# remote_control.net
KiCad netlist of a schematic drawn in EAGLE
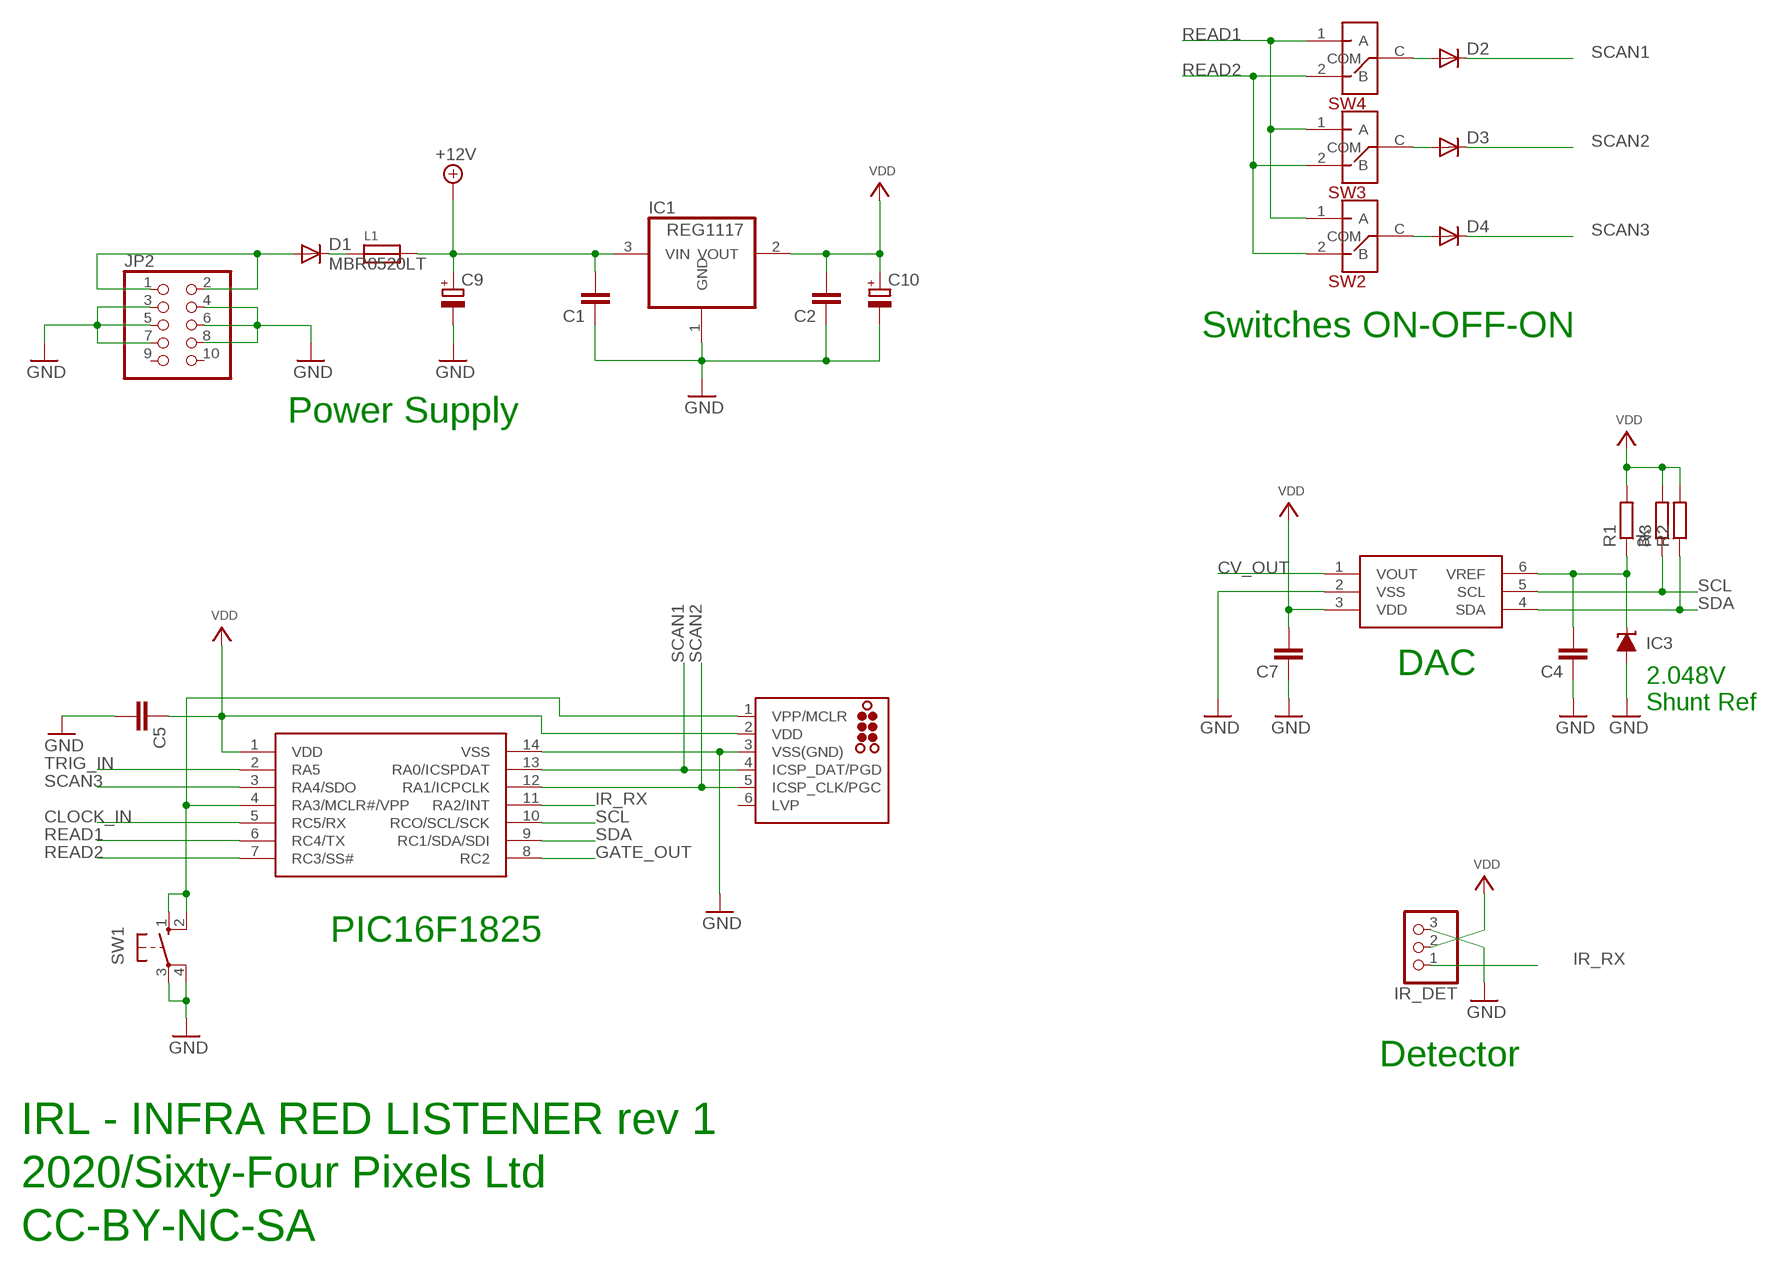
[diagram p0: schematic, sheet 1, part 1 of 2]
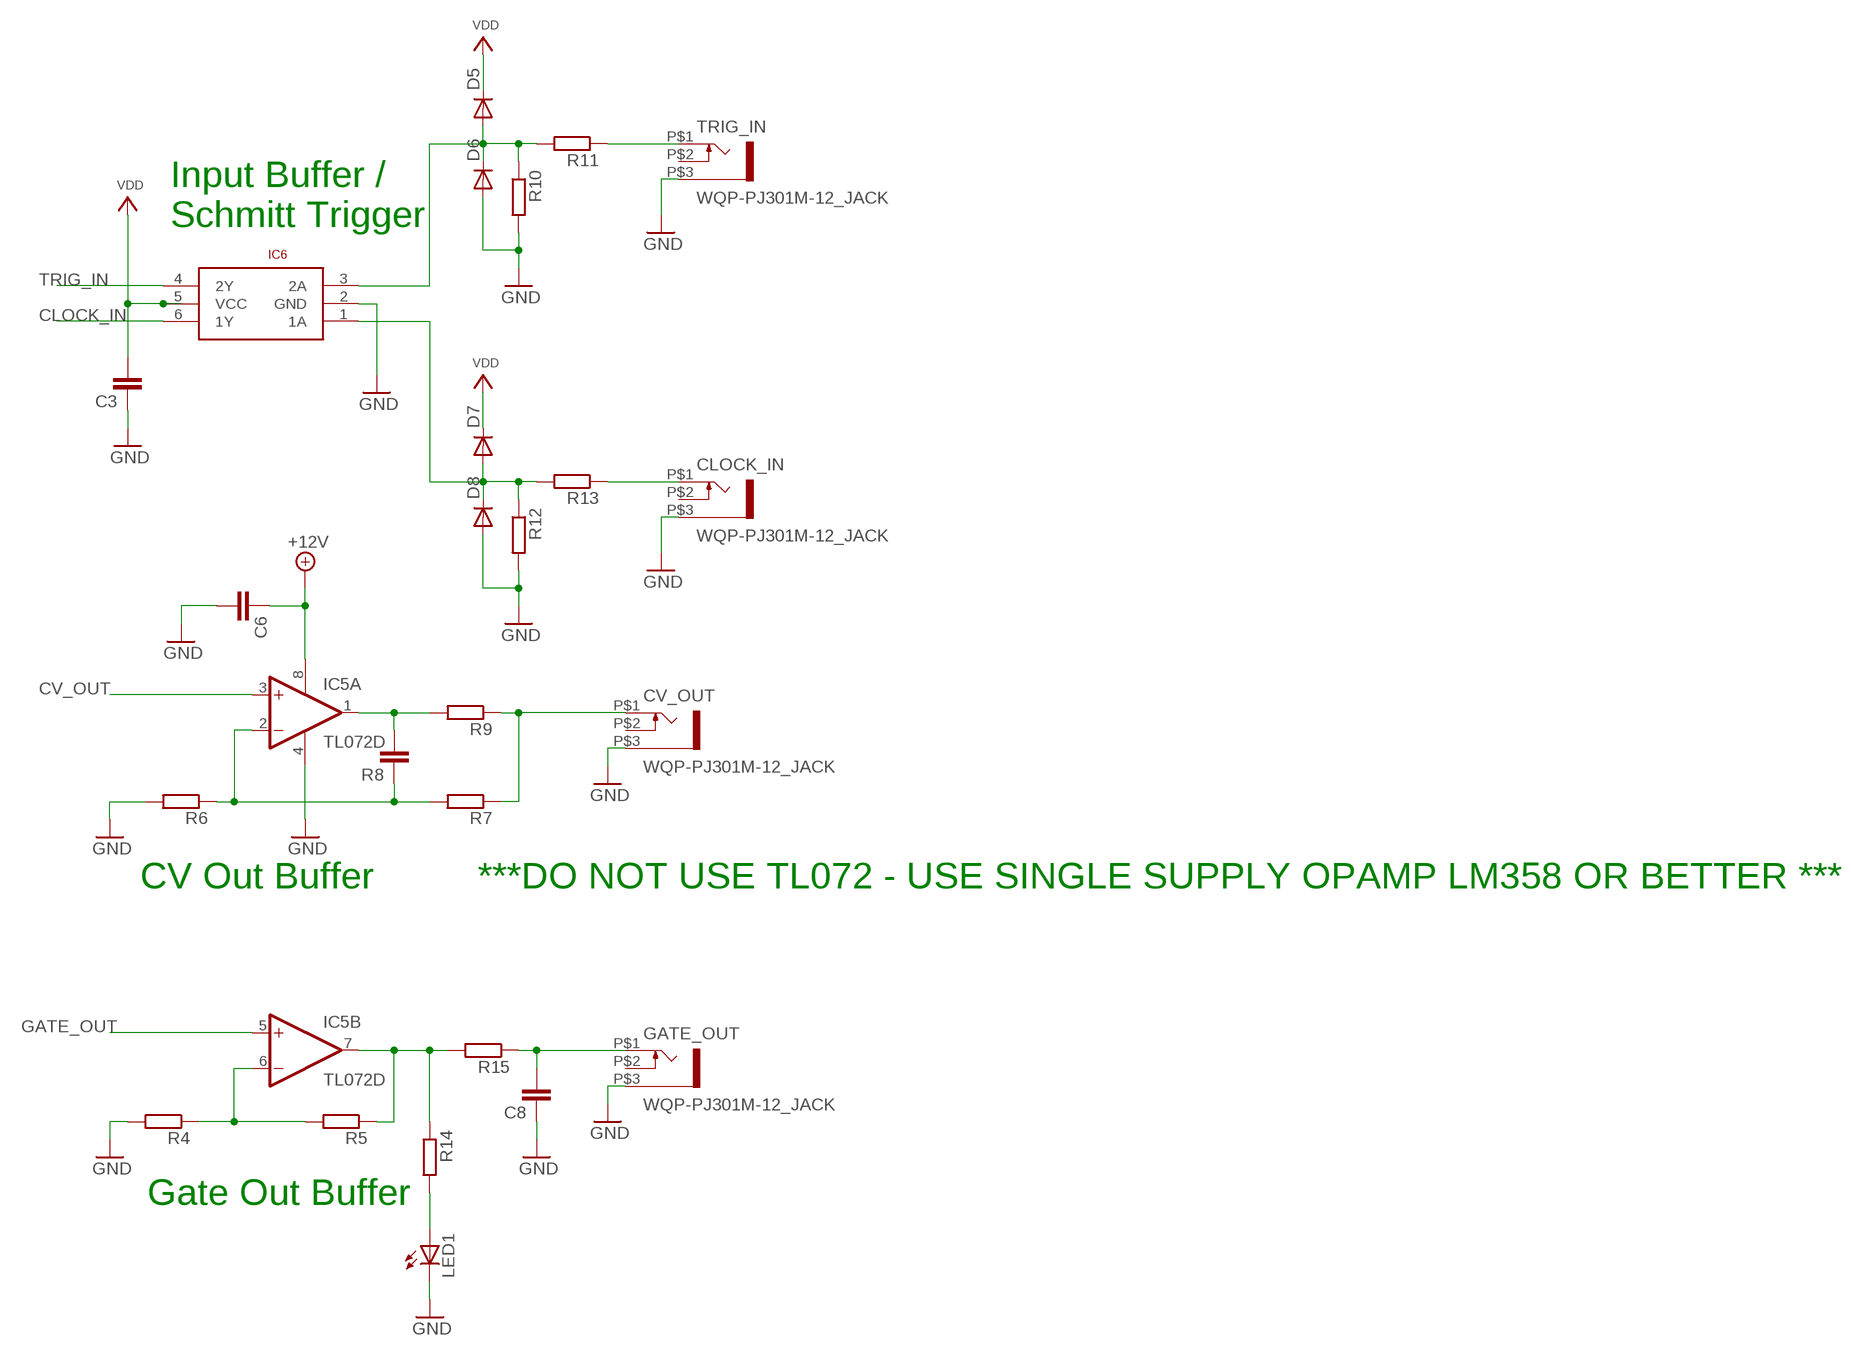
[diagram p1: schematic, sheet 1, part 2 of 2]

(export (version "E")
  (design (tool "Eeschema 10.0.6"))
  (components
    (comp (ref "C1")
      (value "C-EUC0805")
      (footprint "eagle-import:C0805")
      (libsource (lib "eagle-import") (part "C-EUC0805"))
    )
    (comp (ref "C2")
      (value "C-EUC0805")
      (footprint "eagle-import:C0805")
      (libsource (lib "eagle-import") (part "C-EUC0805"))
    )
    (comp (ref "C3")
      (value "C-EUC0805")
      (footprint "eagle-import:C0805")
      (libsource (lib "eagle-import") (part "C-EUC0805"))
    )
    (comp (ref "C4")
      (value "C-EUC0805")
      (footprint "eagle-import:C0805")
      (libsource (lib "eagle-import") (part "C-EUC0805"))
    )
    (comp (ref "C5")
      (value "C-EUC0805")
      (footprint "eagle-import:C0805")
      (libsource (lib "eagle-import") (part "C-EUC0805"))
    )
    (comp (ref "C6")
      (value "C-EUC0805")
      (footprint "eagle-import:C0805")
      (libsource (lib "eagle-import") (part "C-EUC0805"))
    )
    (comp (ref "C7")
      (value "C-EUC0805")
      (footprint "eagle-import:C0805")
      (libsource (lib "eagle-import") (part "C-EUC0805"))
    )
    (comp (ref "C8")
      (value "C-EUC0805")
      (footprint "eagle-import:C0805")
      (libsource (lib "eagle-import") (part "C-EUC0805"))
    )
    (comp (ref "C9")
      (value "CPOL-EUE2-5")
      (footprint "eagle-import:E2-5")
      (libsource (lib "eagle-import") (part "CPOL-EUE2-5"))
    )
    (comp (ref "C10")
      (value "CPOL-EUE2-5")
      (footprint "eagle-import:E2-5")
      (libsource (lib "eagle-import") (part "CPOL-EUE2-5"))
    )
    (comp (ref "CLOCK_IN")
      (value "WQP-PJ301M-12_JACK")
      (footprint "eagle-import:WQP-PJ301M-12_JACK")
      (libsource (lib "eagle-import") (part "WQP-PJ301M-12_JACK"))
    )
    (comp (ref "CV_OUT")
      (value "WQP-PJ301M-12_JACK")
      (footprint "eagle-import:WQP-PJ301M-12_JACK")
      (libsource (lib "eagle-import") (part "WQP-PJ301M-12_JACK"))
    )
    (comp (ref "D1")
      (value "MBR0520LT")
      (footprint "eagle-import:SOD123")
      (libsource (lib "eagle-import") (part "MBR0520LT"))
    )
    (comp (ref "D2")
      (value "TS4148")
      (footprint "eagle-import:D0805")
      (libsource (lib "eagle-import") (part "TS4148"))
    )
    (comp (ref "D3")
      (value "TS4148")
      (footprint "eagle-import:D0805")
      (libsource (lib "eagle-import") (part "TS4148"))
    )
    (comp (ref "D4")
      (value "TS4148")
      (footprint "eagle-import:D0805")
      (libsource (lib "eagle-import") (part "TS4148"))
    )
    (comp (ref "D5")
      (value "TS4148")
      (footprint "eagle-import:D0805")
      (libsource (lib "eagle-import") (part "TS4148"))
    )
    (comp (ref "D6")
      (value "TS4148")
      (footprint "eagle-import:D0805")
      (libsource (lib "eagle-import") (part "TS4148"))
    )
    (comp (ref "D7")
      (value "TS4148")
      (footprint "eagle-import:D0805")
      (libsource (lib "eagle-import") (part "TS4148"))
    )
    (comp (ref "D8")
      (value "TS4148")
      (footprint "eagle-import:D0805")
      (libsource (lib "eagle-import") (part "TS4148"))
    )
    (comp (ref "GATE_OUT")
      (value "WQP-PJ301M-12_JACK")
      (footprint "eagle-import:WQP-PJ301M-12_JACK")
      (libsource (lib "eagle-import") (part "WQP-PJ301M-12_JACK"))
    )
    (comp (ref "IC1")
      (value "REG1117")
      (footprint "eagle-import:SOT223")
      (libsource (lib "eagle-import") (part "REG1117"))
    )
    (comp (ref "IC2")
      (value "PIC16F1825SO14")
      (footprint "eagle-import:SO14")
      (libsource (lib "eagle-import") (part "PIC16F1825SO14"))
    )
    (comp (ref "IC3")
      (value "LM4041A12DBZ")
      (footprint "eagle-import:DBZ_R-PDSO-G3")
      (fields (field (name "MPN") "LM4041A12IDBZR"))
      (libsource (lib "eagle-import") (part "LM4041DBZA12"))
    )
    (comp (ref "IC4")
      (value "MCP4726")
      (footprint "eagle-import:SOT23-6")
      (libsource (lib "eagle-import") (part "MCP4726"))
    )
    (comp (ref "IC5")
      (value "TL072D")
      (footprint "eagle-import:SO08")
      (libsource (lib "eagle-import") (part "TL072D"))
    )
    (comp (ref "IC6")
      (value "SN74LVC2G14")
      (footprint "eagle-import:DBV_R-PDSO-G6")
      (libsource (lib "eagle-import") (part "SN74LVC2G14"))
    )
    (comp (ref "IR_DET")
      (value "PINHD-1X3")
      (footprint "eagle-import:1X03")
      (libsource (lib "eagle-import") (part "PINHD-1X3"))
    )
    (comp (ref "J1")
      (value "TC2030-MCP-NL")
      (footprint "eagle-import:TC2030-MCP-NL")
      (libsource (lib "eagle-import") (part "TC2030-MCP-NL"))
    )
    (comp (ref "JP2")
      (value "PINHD-2X5")
      (footprint "eagle-import:2X05")
      (libsource (lib "eagle-import") (part "PINHD-2X5"))
    )
    (comp (ref "L1")
      (value "FERRITE")
      (footprint "eagle-import:0603")
      (libsource (lib "eagle-import") (part "FERRITE"))
    )
    (comp (ref "LED1")
      (value "LED3MM")
      (footprint "eagle-import:LED3MM")
      (libsource (lib "eagle-import") (part "LED3MM"))
    )
    (comp (ref "R1")
      (value "3k")
      (footprint "eagle-import:R0805")
      (libsource (lib "eagle-import") (part "R-EU_R0805"))
    )
    (comp (ref "R2")
      (value "R-EU_R0805")
      (footprint "eagle-import:R0805")
      (libsource (lib "eagle-import") (part "R-EU_R0805"))
    )
    (comp (ref "R3")
      (value "R-EU_R0805")
      (footprint "eagle-import:R0805")
      (libsource (lib "eagle-import") (part "R-EU_R0805"))
    )
    (comp (ref "R4")
      (value "R-EU_R0805")
      (footprint "eagle-import:R0805")
      (libsource (lib "eagle-import") (part "R-EU_R0805"))
    )
    (comp (ref "R5")
      (value "R-EU_R0805")
      (footprint "eagle-import:R0805")
      (libsource (lib "eagle-import") (part "R-EU_R0805"))
    )
    (comp (ref "R6")
      (value "R-EU_R0805")
      (footprint "eagle-import:R0805")
      (libsource (lib "eagle-import") (part "R-EU_R0805"))
    )
    (comp (ref "R7")
      (value "R-EU_R0805")
      (footprint "eagle-import:R0805")
      (libsource (lib "eagle-import") (part "R-EU_R0805"))
    )
    (comp (ref "R8")
      (value "C-EUC0805")
      (footprint "eagle-import:C0805")
      (libsource (lib "eagle-import") (part "C-EUC0805"))
    )
    (comp (ref "R9")
      (value "R-EU_R0805")
      (footprint "eagle-import:R0805")
      (libsource (lib "eagle-import") (part "R-EU_R0805"))
    )
    (comp (ref "R10")
      (value "R-EU_R0805")
      (footprint "eagle-import:R0805")
      (libsource (lib "eagle-import") (part "R-EU_R0805"))
    )
    (comp (ref "R11")
      (value "R-EU_R0805")
      (footprint "eagle-import:R0805")
      (libsource (lib "eagle-import") (part "R-EU_R0805"))
    )
    (comp (ref "R12")
      (value "R-EU_R0805")
      (footprint "eagle-import:R0805")
      (libsource (lib "eagle-import") (part "R-EU_R0805"))
    )
    (comp (ref "R13")
      (value "R-EU_R0805")
      (footprint "eagle-import:R0805")
      (libsource (lib "eagle-import") (part "R-EU_R0805"))
    )
    (comp (ref "R14")
      (value "R-EU_R0805")
      (footprint "eagle-import:R0805")
      (libsource (lib "eagle-import") (part "R-EU_R0805"))
    )
    (comp (ref "R15")
      (value "R-EU_R0805")
      (footprint "eagle-import:R0805")
      (libsource (lib "eagle-import") (part "R-EU_R0805"))
    )
    (comp (ref "SW1")
      (value "10-XX")
      (footprint "eagle-import:B3F-10XX")
      (fields (field (name "MPN") "B3F-1000"))
      (libsource (lib "eagle-import") (part "10-XX"))
    )
    (comp (ref "SW2")
      (value "MICRO-SPDT")
      (footprint "eagle-import:MICRO-SPDT")
      (libsource (lib "eagle-import") (part "MICRO-SPDT"))
    )
    (comp (ref "SW3")
      (value "MICRO-SPDT")
      (footprint "eagle-import:MICRO-SPDT")
      (libsource (lib "eagle-import") (part "MICRO-SPDT"))
    )
    (comp (ref "SW4")
      (value "MICRO-SPDT")
      (footprint "eagle-import:MICRO-SPDT")
      (libsource (lib "eagle-import") (part "MICRO-SPDT"))
    )
    (comp (ref "TRIG_IN")
      (value "WQP-PJ301M-12_JACK")
      (footprint "eagle-import:WQP-PJ301M-12_JACK")
      (libsource (lib "eagle-import") (part "WQP-PJ301M-12_JACK"))
    )
  )
  (nets
    (net (code "1") (name "+12V") (class "Default")
      (node (ref "C1") (pin "2") (pinfunction "2_2") (pintype "passive"))
      (node (ref "C6") (pin "1") (pinfunction "1_1") (pintype "passive"))
      (node (ref "C9") (pin "+") (pinfunction "+_+") (pintype "passive"))
      (node (ref "IC1") (pin "3") (pinfunction "VIN_3") (pintype "input"))
      (node (ref "IC5") (pin "8") (pinfunction "V+_8") (pintype "power_in"))
      (node (ref "L1") (pin "2") (pinfunction "P$2_2") (pintype "bidirectional"))
    )
    (net (code "2") (name "/CLOCK_IN") (class "Default")
      (node (ref "IC2") (pin "5") (pinfunction "RC5/RX_5") (pintype "bidirectional"))
      (node (ref "IC6") (pin "6") (pinfunction "1Y_6") (pintype "output"))
    )
    (net (code "3") (name "/CV_OUT") (class "Default")
      (node (ref "IC4") (pin "1") (pinfunction "VOUT_1") (pintype "output"))
      (node (ref "IC5") (pin "3") (pinfunction "+IN_3") (pintype "input"))
    )
    (net (code "4") (name "/GATE_OUT") (class "Default")
      (node (ref "IC2") (pin "8") (pinfunction "RC2_8") (pintype "bidirectional"))
      (node (ref "IC5") (pin "5") (pinfunction "+IN_5") (pintype "input"))
    )
    (net (code "5") (name "/IR_RX") (class "Default")
      (node (ref "IC2") (pin "11") (pinfunction "RA2/INT_11") (pintype "bidirectional"))
      (node (ref "IR_DET") (pin "1") (pinfunction "1_1") (pintype "passive"))
    )
    (net (code "6") (name "/READ1") (class "Default")
      (node (ref "IC2") (pin "6") (pinfunction "RC4/TX_6") (pintype "bidirectional"))
      (node (ref "SW2") (pin "1") (pinfunction "A_1") (pintype "bidirectional"))
      (node (ref "SW3") (pin "1") (pinfunction "A_1") (pintype "bidirectional"))
      (node (ref "SW4") (pin "1") (pinfunction "A_1") (pintype "bidirectional"))
    )
    (net (code "7") (name "/READ2") (class "Default")
      (node (ref "IC2") (pin "7") (pinfunction "RC3/SS#_7") (pintype "bidirectional"))
      (node (ref "SW2") (pin "2") (pinfunction "B_2") (pintype "bidirectional"))
      (node (ref "SW3") (pin "2") (pinfunction "B_2") (pintype "bidirectional"))
      (node (ref "SW4") (pin "2") (pinfunction "B_2") (pintype "bidirectional"))
    )
    (net (code "8") (name "/SCAN1") (class "Default")
      (node (ref "D2") (pin "K") (pinfunction "C_K") (pintype "passive"))
      (node (ref "IC2") (pin "13") (pinfunction "RA0/ICSPDAT_13") (pintype "bidirectional"))
      (node (ref "J1") (pin "4") (pinfunction "ICSP_DAT/PGD_4") (pintype "bidirectional"))
    )
    (net (code "9") (name "/SCAN2") (class "Default")
      (node (ref "D3") (pin "K") (pinfunction "C_K") (pintype "passive"))
      (node (ref "IC2") (pin "12") (pinfunction "RA1/ICPCLK_12") (pintype "bidirectional"))
      (node (ref "J1") (pin "5") (pinfunction "ICSP_CLK/PGC_5") (pintype "output"))
    )
    (net (code "10") (name "/SCAN3") (class "Default")
      (node (ref "D4") (pin "K") (pinfunction "C_K") (pintype "passive"))
      (node (ref "IC2") (pin "3") (pinfunction "RA4/SDO_3") (pintype "bidirectional"))
    )
    (net (code "11") (name "/SCL") (class "Default")
      (node (ref "IC2") (pin "10") (pinfunction "RCO/SCL/SCK_10") (pintype "bidirectional"))
      (node (ref "IC4") (pin "5") (pinfunction "SCL_5") (pintype "bidirectional"))
      (node (ref "R3") (pin "1") (pinfunction "1_1") (pintype "passive"))
    )
    (net (code "12") (name "/SDA") (class "Default")
      (node (ref "IC2") (pin "9") (pinfunction "RC1/SDA/SDI_9") (pintype "bidirectional"))
      (node (ref "IC4") (pin "4") (pinfunction "SDA_4") (pintype "bidirectional"))
      (node (ref "R2") (pin "1") (pinfunction "1_1") (pintype "passive"))
    )
    (net (code "13") (name "/TRIG_IN") (class "Default")
      (node (ref "IC2") (pin "2") (pinfunction "RA5_2") (pintype "bidirectional"))
      (node (ref "IC6") (pin "4") (pinfunction "2Y_4") (pintype "output"))
    )
    (net (code "14") (name "GND") (class "Default")
      (node (ref "C1") (pin "1") (pinfunction "1_1") (pintype "passive"))
      (node (ref "C10") (pin "-") (pinfunction "-_-") (pintype "passive"))
      (node (ref "C2") (pin "1") (pinfunction "1_1") (pintype "passive"))
      (node (ref "C3") (pin "1") (pinfunction "1_1") (pintype "passive"))
      (node (ref "C4") (pin "1") (pinfunction "1_1") (pintype "passive"))
      (node (ref "C5") (pin "2") (pinfunction "2_2") (pintype "passive"))
      (node (ref "C6") (pin "2") (pinfunction "2_2") (pintype "passive"))
      (node (ref "C7") (pin "1") (pinfunction "1_1") (pintype "passive"))
      (node (ref "C8") (pin "1") (pinfunction "1_1") (pintype "passive"))
      (node (ref "C9") (pin "-") (pinfunction "-_-") (pintype "passive"))
      (node (ref "CLOCK_IN") (pin "P$3") (pinfunction "1_P$3") (pintype "passive"))
      (node (ref "CV_OUT") (pin "P$3") (pinfunction "1_P$3") (pintype "passive"))
      (node (ref "D6") (pin "A") (pinfunction "A_A") (pintype "passive"))
      (node (ref "D8") (pin "A") (pinfunction "A_A") (pintype "passive"))
      (node (ref "GATE_OUT") (pin "P$3") (pinfunction "1_P$3") (pintype "passive"))
      (node (ref "IC1") (pin "1") (pinfunction "GND_1") (pintype "power_in"))
      (node (ref "IC2") (pin "14") (pinfunction "VSS_14") (pintype "power_in"))
      (node (ref "IC3") (pin "2") (pinfunction "A_2") (pintype "passive"))
      (node (ref "IC4") (pin "2") (pinfunction "VSS_2") (pintype "power_in"))
      (node (ref "IC5") (pin "4") (pinfunction "V-_4") (pintype "power_in"))
      (node (ref "IC6") (pin "2") (pinfunction "GND_2") (pintype "power_in"))
      (node (ref "IR_DET") (pin "3") (pinfunction "3_3") (pintype "passive"))
      (node (ref "J1") (pin "3") (pinfunction "VSS(GND)_3") (pintype "power_in"))
      (node (ref "JP2") (pin "3") (pinfunction "3_3") (pintype "passive"))
      (node (ref "JP2") (pin "4") (pinfunction "4_4") (pintype "passive"))
      (node (ref "JP2") (pin "5") (pinfunction "5_5") (pintype "passive"))
      (node (ref "JP2") (pin "6") (pinfunction "6_6") (pintype "passive"))
      (node (ref "JP2") (pin "7") (pinfunction "7_7") (pintype "passive"))
      (node (ref "JP2") (pin "8") (pinfunction "8_8") (pintype "passive"))
      (node (ref "LED1") (pin "K") (pinfunction "C_K") (pintype "passive"))
      (node (ref "R10") (pin "2") (pinfunction "2_2") (pintype "passive"))
      (node (ref "R12") (pin "2") (pinfunction "2_2") (pintype "passive"))
      (node (ref "R4") (pin "2") (pinfunction "2_2") (pintype "passive"))
      (node (ref "R6") (pin "2") (pinfunction "2_2") (pintype "passive"))
      (node (ref "SW1") (pin "3") (pinfunction "P_3") (pintype "passive"))
      (node (ref "SW1") (pin "4") (pinfunction "P1_4") (pintype "passive"))
      (node (ref "TRIG_IN") (pin "P$3") (pinfunction "1_P$3") (pintype "passive"))
    )
    (net (code "15") (name "Net-(CLOCK_IN-2)") (class "Default")
      (node (ref "CLOCK_IN") (pin "P$1") (pinfunction "2_P$1") (pintype "passive"))
      (node (ref "R13") (pin "1") (pinfunction "1_1") (pintype "passive"))
    )
    (net (code "16") (name "Net-(CV_OUT-2)") (class "Default")
      (node (ref "CV_OUT") (pin "P$1") (pinfunction "2_P$1") (pintype "passive"))
      (node (ref "R7") (pin "1") (pinfunction "1_1") (pintype "passive"))
      (node (ref "R9") (pin "1") (pinfunction "1_1") (pintype "passive"))
    )
    (net (code "17") (name "Net-(D1-PadA)") (class "Default")
      (node (ref "D1") (pin "A") (pinfunction "A_A") (pintype "passive"))
      (node (ref "JP2") (pin "1") (pinfunction "1_1") (pintype "passive"))
      (node (ref "JP2") (pin "2") (pinfunction "2_2") (pintype "passive"))
    )
    (net (code "18") (name "Net-(D6-C)") (class "Default")
      (node (ref "D5") (pin "A") (pinfunction "A_A") (pintype "passive"))
      (node (ref "D6") (pin "K") (pinfunction "C_K") (pintype "passive"))
      (node (ref "IC6") (pin "3") (pinfunction "2A_3") (pintype "input"))
      (node (ref "R10") (pin "1") (pinfunction "1_1") (pintype "passive"))
      (node (ref "R11") (pin "2") (pinfunction "2_2") (pintype "passive"))
    )
    (net (code "19") (name "Net-(D8-C)") (class "Default")
      (node (ref "D7") (pin "A") (pinfunction "A_A") (pintype "passive"))
      (node (ref "D8") (pin "K") (pinfunction "C_K") (pintype "passive"))
      (node (ref "IC6") (pin "1") (pinfunction "1A_1") (pintype "input"))
      (node (ref "R12") (pin "1") (pinfunction "1_1") (pintype "passive"))
      (node (ref "R13") (pin "2") (pinfunction "2_2") (pintype "passive"))
    )
    (net (code "20") (name "Net-(GATE_OUT-2)") (class "Default")
      (node (ref "C8") (pin "2") (pinfunction "2_2") (pintype "passive"))
      (node (ref "GATE_OUT") (pin "P$1") (pinfunction "2_P$1") (pintype "passive"))
      (node (ref "R15") (pin "1") (pinfunction "1_1") (pintype "passive"))
    )
    (net (code "21") (name "Net-(IC2-RA3{slash}MCLR#{slash}VPP)") (class "Default")
      (node (ref "IC2") (pin "4") (pinfunction "RA3/MCLR#/VPP_4") (pintype "input"))
      (node (ref "J1") (pin "1") (pinfunction "VPP/MCLR_1") (pintype "passive"))
      (node (ref "SW1") (pin "1") (pinfunction "S_1") (pintype "passive"))
      (node (ref "SW1") (pin "2") (pinfunction "S1_2") (pintype "passive"))
    )
    (net (code "22") (name "Net-(IC3-C)") (class "Default")
      (node (ref "C4") (pin "2") (pinfunction "2_2") (pintype "passive"))
      (node (ref "IC3") (pin "1") (pinfunction "C_1") (pintype "passive"))
      (node (ref "IC4") (pin "6") (pinfunction "VREF_6") (pintype "input"))
      (node (ref "R1") (pin "1") (pinfunction "1_1") (pintype "passive"))
    )
    (net (code "23") (name "Net-(IC5A--IN)") (class "Default")
      (node (ref "IC5") (pin "2") (pinfunction "-IN_2") (pintype "input"))
      (node (ref "R6") (pin "1") (pinfunction "1_1") (pintype "passive"))
      (node (ref "R7") (pin "2") (pinfunction "2_2") (pintype "passive"))
      (node (ref "R8") (pin "1") (pinfunction "1_1") (pintype "passive"))
    )
    (net (code "24") (name "Net-(IC5A-OUT)") (class "Default")
      (node (ref "IC5") (pin "1") (pinfunction "OUT_1") (pintype "output"))
      (node (ref "R8") (pin "2") (pinfunction "2_2") (pintype "passive"))
      (node (ref "R9") (pin "2") (pinfunction "2_2") (pintype "passive"))
    )
    (net (code "25") (name "Net-(IC5B--IN)") (class "Default")
      (node (ref "IC5") (pin "6") (pinfunction "-IN_6") (pintype "input"))
      (node (ref "R4") (pin "1") (pinfunction "1_1") (pintype "passive"))
      (node (ref "R5") (pin "2") (pinfunction "2_2") (pintype "passive"))
    )
    (net (code "26") (name "Net-(IC5B-OUT)") (class "Default")
      (node (ref "IC5") (pin "7") (pinfunction "OUT_7") (pintype "output"))
      (node (ref "R14") (pin "1") (pinfunction "1_1") (pintype "passive"))
      (node (ref "R15") (pin "2") (pinfunction "2_2") (pintype "passive"))
      (node (ref "R5") (pin "1") (pinfunction "1_1") (pintype "passive"))
    )
    (net (code "27") (name "Net-(L1-P$1)") (class "Default")
      (node (ref "D1") (pin "C") (pinfunction "C_C") (pintype "passive"))
      (node (ref "L1") (pin "1") (pinfunction "P$1_1") (pintype "bidirectional"))
    )
    (net (code "28") (name "Net-(LED1-PadA)") (class "Default")
      (node (ref "LED1") (pin "A") (pinfunction "A_A") (pintype "passive"))
      (node (ref "R14") (pin "2") (pinfunction "2_2") (pintype "passive"))
    )
    (net (code "29") (name "Net-(SW2-COM)") (class "Default")
      (node (ref "D4") (pin "A") (pinfunction "A_A") (pintype "passive"))
      (node (ref "SW2") (pin "C") (pinfunction "COM_C") (pintype "bidirectional"))
    )
    (net (code "30") (name "Net-(SW3-COM)") (class "Default")
      (node (ref "D3") (pin "A") (pinfunction "A_A") (pintype "passive"))
      (node (ref "SW3") (pin "C") (pinfunction "COM_C") (pintype "bidirectional"))
    )
    (net (code "31") (name "Net-(SW4-COM)") (class "Default")
      (node (ref "D2") (pin "A") (pinfunction "A_A") (pintype "passive"))
      (node (ref "SW4") (pin "C") (pinfunction "COM_C") (pintype "bidirectional"))
    )
    (net (code "32") (name "Net-(TRIG_IN-2)") (class "Default")
      (node (ref "R11") (pin "1") (pinfunction "1_1") (pintype "passive"))
      (node (ref "TRIG_IN") (pin "P$1") (pinfunction "2_P$1") (pintype "passive"))
    )
    (net (code "33") (name "VDD") (class "Default")
      (node (ref "C10") (pin "+") (pinfunction "+_+") (pintype "passive"))
      (node (ref "C2") (pin "2") (pinfunction "2_2") (pintype "passive"))
      (node (ref "C3") (pin "2") (pinfunction "2_2") (pintype "passive"))
      (node (ref "C5") (pin "1") (pinfunction "1_1") (pintype "passive"))
      (node (ref "C7") (pin "2") (pinfunction "2_2") (pintype "passive"))
      (node (ref "D5") (pin "K") (pinfunction "C_K") (pintype "passive"))
      (node (ref "D7") (pin "K") (pinfunction "C_K") (pintype "passive"))
      (node (ref "IC1") (pin "2") (pinfunction "VOUT_2") (pintype "output"))
      (node (ref "IC2") (pin "1") (pinfunction "VDD_1") (pintype "power_in"))
      (node (ref "IC4") (pin "3") (pinfunction "VDD_3") (pintype "power_in"))
      (node (ref "IC6") (pin "5") (pinfunction "VCC_5") (pintype "power_in"))
      (node (ref "IR_DET") (pin "2") (pinfunction "2_2") (pintype "passive"))
      (node (ref "J1") (pin "2") (pinfunction "VDD_2") (pintype "power_in"))
      (node (ref "R1") (pin "2") (pinfunction "2_2") (pintype "passive"))
      (node (ref "R2") (pin "2") (pinfunction "2_2") (pintype "passive"))
      (node (ref "R3") (pin "2") (pinfunction "2_2") (pintype "passive"))
    )
    (net (code "34") (name "unconnected-(CLOCK_IN-3-PadP$2)") (class "Default")
      (node (ref "CLOCK_IN") (pin "P$2") (pinfunction "3_P$2") (pintype "passive"))
    )
    (net (code "35") (name "unconnected-(CV_OUT-3-PadP$2)") (class "Default")
      (node (ref "CV_OUT") (pin "P$2") (pinfunction "3_P$2") (pintype "passive"))
    )
    (net (code "36") (name "unconnected-(GATE_OUT-3-PadP$2)") (class "Default")
      (node (ref "GATE_OUT") (pin "P$2") (pinfunction "3_P$2") (pintype "passive"))
    )
    (net (code "37") (name "unconnected-(J1-LVP-Pad6)") (class "Default")
      (node (ref "J1") (pin "6") (pinfunction "LVP_6") (pintype "bidirectional"))
    )
    (net (code "38") (name "unconnected-(JP2-Pad9)") (class "Default")
      (node (ref "JP2") (pin "9") (pinfunction "9_9") (pintype "passive"))
    )
    (net (code "39") (name "unconnected-(JP2-Pad10)") (class "Default")
      (node (ref "JP2") (pin "10") (pinfunction "10_10") (pintype "passive"))
    )
    (net (code "40") (name "unconnected-(TRIG_IN-3-PadP$2)") (class "Default")
      (node (ref "TRIG_IN") (pin "P$2") (pinfunction "3_P$2") (pintype "passive"))
    )
  )
)
